# XMC4800-Core.net
KiCad netlist of a schematic drawn in Altium Designer
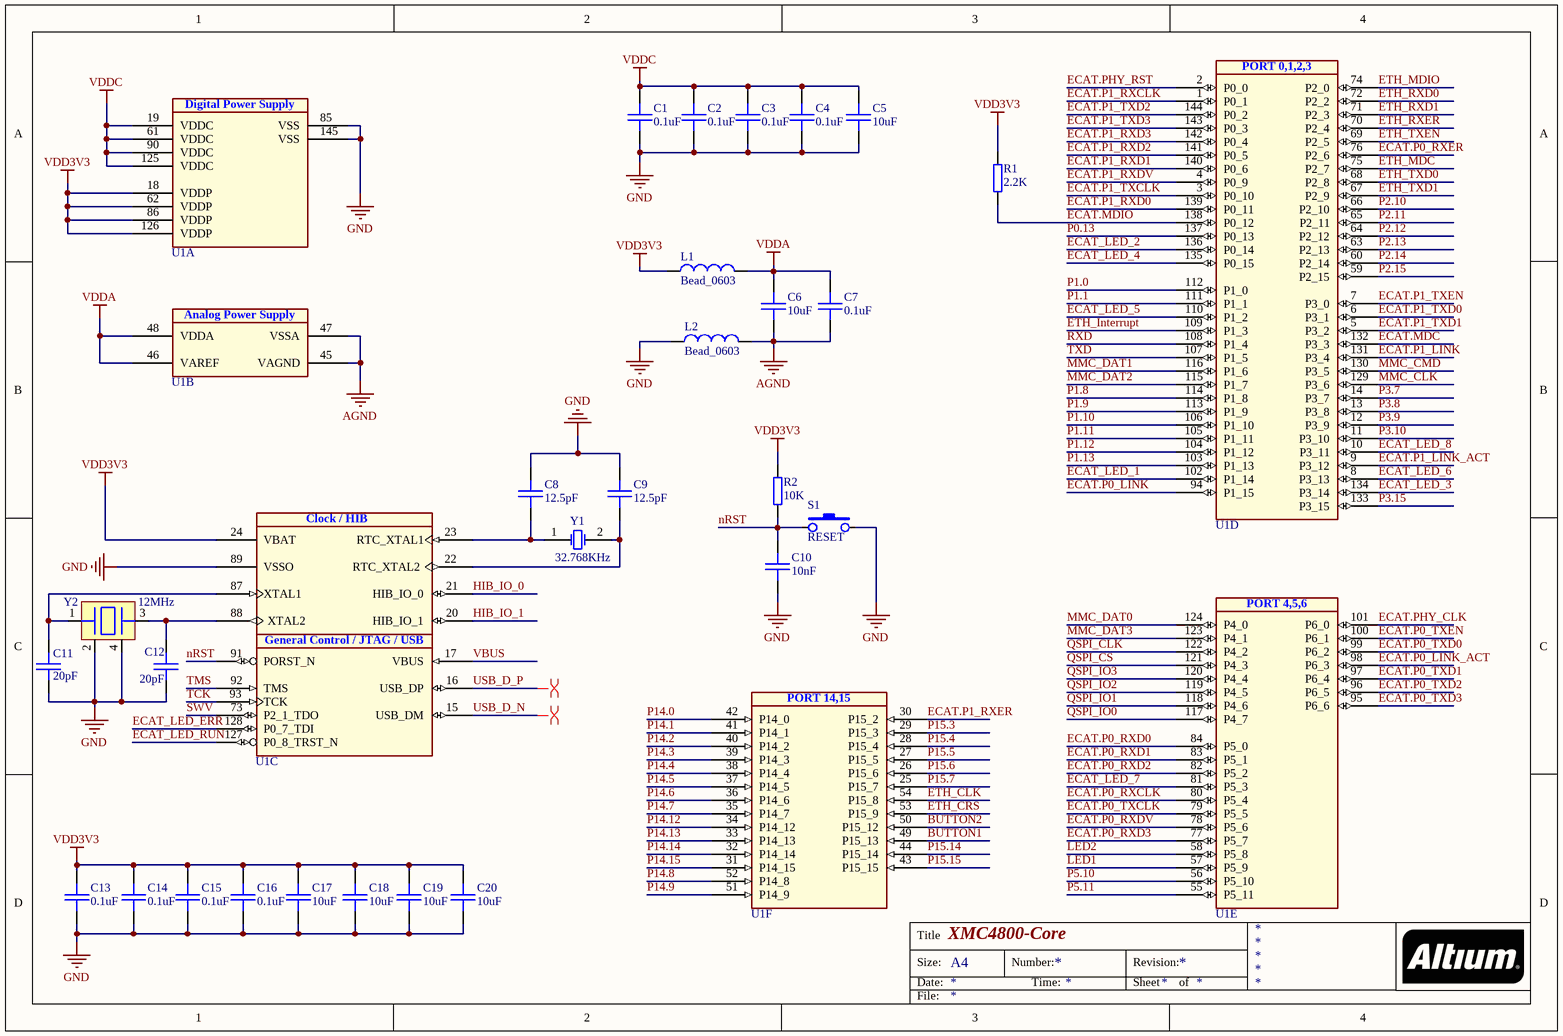
[diagram p0: XMC4800-Core.SchDoc]

(export (version "E")
  (design (tool "Eeschema 10.0.6"))
  (components
    (comp (ref "C1")
      (value "0.1uF")
      (footprint "CAP-0603")
      (description "陶瓷贴片电容0603")
      (fields (field (name "TOLERANCE") "10%") (field (name "VOLTAGE") "50V"))
      (libsource (lib "momo") (part "C_0603"))
    )
    (comp (ref "C2")
      (value "0.1uF")
      (footprint "CAP-0603")
      (description "陶瓷贴片电容0603")
      (fields (field (name "TOLERANCE") "10%") (field (name "VOLTAGE") "50V"))
      (libsource (lib "momo") (part "C_0603"))
    )
    (comp (ref "C3")
      (value "0.1uF")
      (footprint "CAP-0603")
      (description "陶瓷贴片电容0603")
      (fields (field (name "TOLERANCE") "10%") (field (name "VOLTAGE") "50V"))
      (libsource (lib "momo") (part "C_0603"))
    )
    (comp (ref "C4")
      (value "0.1uF")
      (footprint "CAP-0603")
      (description "陶瓷贴片电容0603")
      (fields (field (name "TOLERANCE") "10%") (field (name "VOLTAGE") "50V"))
      (libsource (lib "momo") (part "C_0603"))
    )
    (comp (ref "C5")
      (value "10uF")
      (footprint "CAP-0603")
      (description "陶瓷贴片电容0603")
      (fields (field (name "TOLERANCE") "10%") (field (name "VOLTAGE") "50V"))
      (libsource (lib "momo") (part "C_0603"))
    )
    (comp (ref "C6")
      (value "10uF")
      (footprint "CAP-0603")
      (description "陶瓷贴片电容0603")
      (fields (field (name "TOLERANCE") "10%") (field (name "VOLTAGE") "50V"))
      (libsource (lib "momo") (part "C_0603"))
    )
    (comp (ref "C7")
      (value "0.1uF")
      (footprint "CAP-0603")
      (description "陶瓷贴片电容0603")
      (fields (field (name "TOLERANCE") "10%") (field (name "VOLTAGE") "50V"))
      (libsource (lib "momo") (part "C_0603"))
    )
    (comp (ref "C8")
      (value "12.5pF")
      (footprint "CAP-0603")
      (description "陶瓷贴片电容0603")
      (fields (field (name "TOLERANCE") "10%") (field (name "VOLTAGE") "50V"))
      (libsource (lib "momo") (part "C_0603"))
    )
    (comp (ref "C9")
      (value "12.5pF")
      (footprint "CAP-0603")
      (description "陶瓷贴片电容0603")
      (fields (field (name "TOLERANCE") "10%") (field (name "VOLTAGE") "50V"))
      (libsource (lib "momo") (part "C_0603"))
    )
    (comp (ref "C10")
      (value "10nF")
      (footprint "CAP-0603")
      (description "陶瓷贴片电容0603")
      (fields (field (name "TOLERANCE") "10%") (field (name "VOLTAGE") "50V"))
      (libsource (lib "momo") (part "C_0603"))
    )
    (comp (ref "C11")
      (value "20pF")
      (footprint "CAP-0603")
      (description "陶瓷贴片电容0603")
      (fields (field (name "TOLERANCE") "10%") (field (name "VOLTAGE") "50V"))
      (libsource (lib "momo") (part "C_0603"))
    )
    (comp (ref "C12")
      (value "20pF")
      (footprint "CAP-0603")
      (description "陶瓷贴片电容0603")
      (fields (field (name "TOLERANCE") "10%") (field (name "VOLTAGE") "50V"))
      (libsource (lib "momo") (part "C_0603"))
    )
    (comp (ref "C13")
      (value "0.1uF")
      (footprint "CAP-0603")
      (description "陶瓷贴片电容0603")
      (fields (field (name "TOLERANCE") "10%") (field (name "VOLTAGE") "50V"))
      (libsource (lib "momo") (part "C_0603"))
    )
    (comp (ref "C14")
      (value "0.1uF")
      (footprint "CAP-0603")
      (description "陶瓷贴片电容0603")
      (fields (field (name "TOLERANCE") "10%") (field (name "VOLTAGE") "50V"))
      (libsource (lib "momo") (part "C_0603"))
    )
    (comp (ref "C15")
      (value "0.1uF")
      (footprint "CAP-0603")
      (description "陶瓷贴片电容0603")
      (fields (field (name "TOLERANCE") "10%") (field (name "VOLTAGE") "50V"))
      (libsource (lib "momo") (part "C_0603"))
    )
    (comp (ref "C16")
      (value "0.1uF")
      (footprint "CAP-0603")
      (description "陶瓷贴片电容0603")
      (fields (field (name "TOLERANCE") "10%") (field (name "VOLTAGE") "50V"))
      (libsource (lib "momo") (part "C_0603"))
    )
    (comp (ref "C17")
      (value "10uF")
      (footprint "CAP-0603")
      (description "陶瓷贴片电容0603")
      (fields (field (name "TOLERANCE") "10%") (field (name "VOLTAGE") "50V"))
      (libsource (lib "momo") (part "C_0603"))
    )
    (comp (ref "C18")
      (value "10uF")
      (footprint "CAP-0603")
      (description "陶瓷贴片电容0603")
      (fields (field (name "TOLERANCE") "10%") (field (name "VOLTAGE") "50V"))
      (libsource (lib "momo") (part "C_0603"))
    )
    (comp (ref "C19")
      (value "10uF")
      (footprint "CAP-0603")
      (description "陶瓷贴片电容0603")
      (fields (field (name "TOLERANCE") "10%") (field (name "VOLTAGE") "50V"))
      (libsource (lib "momo") (part "C_0603"))
    )
    (comp (ref "C20")
      (value "10uF")
      (footprint "CAP-0603")
      (description "陶瓷贴片电容0603")
      (fields (field (name "TOLERANCE") "10%") (field (name "VOLTAGE") "50V"))
      (libsource (lib "momo") (part "C_0603"))
    )
    (comp (ref "L1")
      (value "Bead_0603")
      (footprint "L-0603")
      (description "贴片磁珠0603")
      (libsource (lib "momo") (part "Bead_0603"))
    )
    (comp (ref "L2")
      (value "Bead_0603")
      (footprint "L-0603")
      (description "贴片磁珠0603")
      (libsource (lib "momo") (part "Bead_0603"))
    )
    (comp (ref "R1")
      (value "2.2K")
      (footprint "RES-0603")
      (description "贴片电阻0603")
      (fields (field (name "TOLERANCE") "5%") (field (name "VOLTAGE") "50V"))
      (libsource (lib "momo") (part "R_0603"))
    )
    (comp (ref "R2")
      (value "10K")
      (footprint "RES-0603")
      (description "贴片电阻0603")
      (fields (field (name "TOLERANCE") "5%") (field (name "VOLTAGE") "50V"))
      (libsource (lib "momo") (part "R_0603"))
    )
    (comp (ref "S1")
      (value "RESET")
      (footprint "KEY_3X4X2")
      (description "轻触开关3X4X2")
      (libsource (lib "momo") (part "KEY"))
    )
    (comp (ref "U1")
      (value "XMC4800-F144F1024")
      (footprint "QFP50P2200X2200X160-145N-2")
      (fields (field (name "MANUFACTURER") "Infineon Technologies"))
      (libsource (lib "momo") (part "XMC4800-F144F1024"))
    )
    (comp (ref "Y1")
      (value "32.768KHz")
      (footprint "FC-135(3215)")
      (description "32.768KHz时钟晶振")
      (libsource (lib "momo") (part "OSC_32768"))
    )
    (comp (ref "Y2")
      (value "12MHz")
      (footprint "LC-SMD-3225_4P")
      (description "贴片无源晶振(3225)")
      (libsource (lib "momo") (part "XTAL_PASSIVE"))
    )
  )
  (nets
    (net (code "1") (name "/BUTTON1") (class "Default")
      (node (ref "U1") (pin "49") (pinfunction "P15_13_49") (pintype "input"))
    )
    (net (code "2") (name "/BUTTON2") (class "Default")
      (node (ref "U1") (pin "50") (pinfunction "P15_12_50") (pintype "input"))
    )
    (net (code "3") (name "/ECAT.MDC") (class "Default")
      (node (ref "U1") (pin "132") (pinfunction "P3_3_132") (pintype "bidirectional"))
    )
    (net (code "4") (name "/ECAT.MDIO") (class "Default")
      (node (ref "R1") (pin "1") (pinfunction "1_1") (pintype "passive"))
      (node (ref "U1") (pin "138") (pinfunction "P0_12_138") (pintype "bidirectional"))
    )
    (net (code "5") (name "/ECAT.P0_LINK") (class "Default")
      (node (ref "U1") (pin "94") (pinfunction "P1_15_94") (pintype "bidirectional"))
    )
    (net (code "6") (name "/ECAT.P0_LINK_ACT") (class "Default")
      (node (ref "U1") (pin "98") (pinfunction "P6_3_98") (pintype "bidirectional"))
    )
    (net (code "7") (name "/ECAT.P0_RXCLK") (class "Default")
      (node (ref "U1") (pin "80") (pinfunction "P5_4_80") (pintype "bidirectional"))
    )
    (net (code "8") (name "/ECAT.P0_RXD0") (class "Default")
      (node (ref "U1") (pin "84") (pinfunction "P5_0_84") (pintype "bidirectional"))
    )
    (net (code "9") (name "/ECAT.P0_RXD1") (class "Default")
      (node (ref "U1") (pin "83") (pinfunction "P5_1_83") (pintype "bidirectional"))
    )
    (net (code "10") (name "/ECAT.P0_RXD2") (class "Default")
      (node (ref "U1") (pin "82") (pinfunction "P5_2_82") (pintype "bidirectional"))
    )
    (net (code "11") (name "/ECAT.P0_RXD3") (class "Default")
      (node (ref "U1") (pin "77") (pinfunction "P5_7_77") (pintype "bidirectional"))
    )
    (net (code "12") (name "/ECAT.P0_RXDV") (class "Default")
      (node (ref "U1") (pin "78") (pinfunction "P5_6_78") (pintype "bidirectional"))
    )
    (net (code "13") (name "/ECAT.P0_RXER") (class "Default")
      (node (ref "U1") (pin "76") (pinfunction "P2_6_76") (pintype "bidirectional"))
    )
    (net (code "14") (name "/ECAT.P0_TXCLK") (class "Default")
      (node (ref "U1") (pin "79") (pinfunction "P5_5_79") (pintype "bidirectional"))
    )
    (net (code "15") (name "/ECAT.P0_TXD0") (class "Default")
      (node (ref "U1") (pin "99") (pinfunction "P6_2_99") (pintype "bidirectional"))
    )
    (net (code "16") (name "/ECAT.P0_TXD1") (class "Default")
      (node (ref "U1") (pin "97") (pinfunction "P6_4_97") (pintype "bidirectional"))
    )
    (net (code "17") (name "/ECAT.P0_TXD2") (class "Default")
      (node (ref "U1") (pin "96") (pinfunction "P6_5_96") (pintype "bidirectional"))
    )
    (net (code "18") (name "/ECAT.P0_TXD3") (class "Default")
      (node (ref "U1") (pin "95") (pinfunction "P6_6_95") (pintype "bidirectional"))
    )
    (net (code "19") (name "/ECAT.P0_TXEN") (class "Default")
      (node (ref "U1") (pin "100") (pinfunction "P6_1_100") (pintype "bidirectional"))
    )
    (net (code "20") (name "/ECAT.P1_LINK") (class "Default")
      (node (ref "U1") (pin "131") (pinfunction "P3_4_131") (pintype "bidirectional"))
    )
    (net (code "21") (name "/ECAT.P1_LINK_ACT") (class "Default")
      (node (ref "U1") (pin "9") (pinfunction "P3_12_9") (pintype "bidirectional"))
    )
    (net (code "22") (name "/ECAT.P1_RXCLK") (class "Default")
      (node (ref "U1") (pin "1") (pinfunction "P0_1_1") (pintype "bidirectional"))
    )
    (net (code "23") (name "/ECAT.P1_RXD0") (class "Default")
      (node (ref "U1") (pin "139") (pinfunction "P0_11_139") (pintype "bidirectional"))
    )
    (net (code "24") (name "/ECAT.P1_RXD1") (class "Default")
      (node (ref "U1") (pin "140") (pinfunction "P0_6_140") (pintype "bidirectional"))
    )
    (net (code "25") (name "/ECAT.P1_RXD2") (class "Default")
      (node (ref "U1") (pin "141") (pinfunction "P0_5_141") (pintype "bidirectional"))
    )
    (net (code "26") (name "/ECAT.P1_RXD3") (class "Default")
      (node (ref "U1") (pin "142") (pinfunction "P0_4_142") (pintype "bidirectional"))
    )
    (net (code "27") (name "/ECAT.P1_RXDV") (class "Default")
      (node (ref "U1") (pin "4") (pinfunction "P0_9_4") (pintype "bidirectional"))
    )
    (net (code "28") (name "/ECAT.P1_RXER") (class "Default")
      (node (ref "U1") (pin "30") (pinfunction "P15_2_30") (pintype "input"))
    )
    (net (code "29") (name "/ECAT.P1_TXCLK") (class "Default")
      (node (ref "U1") (pin "3") (pinfunction "P0_10_3") (pintype "bidirectional"))
    )
    (net (code "30") (name "/ECAT.P1_TXD0") (class "Default")
      (node (ref "U1") (pin "6") (pinfunction "P3_1_6") (pintype "bidirectional"))
    )
    (net (code "31") (name "/ECAT.P1_TXD1") (class "Default")
      (node (ref "U1") (pin "5") (pinfunction "P3_2_5") (pintype "bidirectional"))
    )
    (net (code "32") (name "/ECAT.P1_TXD2") (class "Default")
      (node (ref "U1") (pin "144") (pinfunction "P0_2_144") (pintype "bidirectional"))
    )
    (net (code "33") (name "/ECAT.P1_TXD3") (class "Default")
      (node (ref "U1") (pin "143") (pinfunction "P0_3_143") (pintype "bidirectional"))
    )
    (net (code "34") (name "/ECAT.P1_TXEN") (class "Default")
      (node (ref "U1") (pin "7") (pinfunction "P3_0_7") (pintype "bidirectional"))
    )
    (net (code "35") (name "/ECAT.PHY_CLK") (class "Default")
      (node (ref "U1") (pin "101") (pinfunction "P6_0_101") (pintype "bidirectional"))
    )
    (net (code "36") (name "/ECAT.PHY_RST") (class "Default")
      (node (ref "U1") (pin "2") (pinfunction "P0_0_2") (pintype "bidirectional"))
    )
    (net (code "37") (name "/ECAT_LED_1") (class "Default")
      (node (ref "U1") (pin "102") (pinfunction "P1_14_102") (pintype "bidirectional"))
    )
    (net (code "38") (name "/ECAT_LED_2") (class "Default")
      (node (ref "U1") (pin "136") (pinfunction "P0_14_136") (pintype "bidirectional"))
    )
    (net (code "39") (name "/ECAT_LED_3") (class "Default")
      (node (ref "U1") (pin "134") (pinfunction "P3_14_134") (pintype "bidirectional"))
    )
    (net (code "40") (name "/ECAT_LED_4") (class "Default")
      (node (ref "U1") (pin "135") (pinfunction "P0_15_135") (pintype "bidirectional"))
    )
    (net (code "41") (name "/ECAT_LED_5") (class "Default")
      (node (ref "U1") (pin "110") (pinfunction "P1_2_110") (pintype "bidirectional"))
    )
    (net (code "42") (name "/ECAT_LED_6") (class "Default")
      (node (ref "U1") (pin "8") (pinfunction "P3_13_8") (pintype "bidirectional"))
    )
    (net (code "43") (name "/ECAT_LED_7") (class "Default")
      (node (ref "U1") (pin "81") (pinfunction "P5_3_81") (pintype "bidirectional"))
    )
    (net (code "44") (name "/ECAT_LED_8") (class "Default")
      (node (ref "U1") (pin "10") (pinfunction "P3_11_10") (pintype "bidirectional"))
    )
    (net (code "45") (name "/ECAT_LED_ERR") (class "Default")
      (node (ref "U1") (pin "128") (pinfunction "P0_7_TDI_128") (pintype "bidirectional"))
    )
    (net (code "46") (name "/ECAT_LED_RUN") (class "Default")
      (node (ref "U1") (pin "127") (pinfunction "P0_8_TRST_N_127") (pintype "bidirectional"))
    )
    (net (code "47") (name "/ETH_CLK") (class "Default")
      (node (ref "U1") (pin "54") (pinfunction "P15_8_54") (pintype "input"))
    )
    (net (code "48") (name "/ETH_CRS") (class "Default")
      (node (ref "U1") (pin "53") (pinfunction "P15_9_53") (pintype "input"))
    )
    (net (code "49") (name "/ETH_Interrupt") (class "Default")
      (node (ref "U1") (pin "109") (pinfunction "P1_3_109") (pintype "bidirectional"))
    )
    (net (code "50") (name "/ETH_MDC") (class "Default")
      (node (ref "U1") (pin "75") (pinfunction "P2_7_75") (pintype "bidirectional"))
    )
    (net (code "51") (name "/ETH_MDIO") (class "Default")
      (node (ref "U1") (pin "74") (pinfunction "P2_0_74") (pintype "bidirectional"))
    )
    (net (code "52") (name "/ETH_RXD0") (class "Default")
      (node (ref "U1") (pin "72") (pinfunction "P2_2_72") (pintype "bidirectional"))
    )
    (net (code "53") (name "/ETH_RXD1") (class "Default")
      (node (ref "U1") (pin "71") (pinfunction "P2_3_71") (pintype "bidirectional"))
    )
    (net (code "54") (name "/ETH_RXER") (class "Default")
      (node (ref "U1") (pin "70") (pinfunction "P2_4_70") (pintype "bidirectional"))
    )
    (net (code "55") (name "/ETH_TXD0") (class "Default")
      (node (ref "U1") (pin "68") (pinfunction "P2_8_68") (pintype "bidirectional"))
    )
    (net (code "56") (name "/ETH_TXD1") (class "Default")
      (node (ref "U1") (pin "67") (pinfunction "P2_9_67") (pintype "bidirectional"))
    )
    (net (code "57") (name "/ETH_TXEN") (class "Default")
      (node (ref "U1") (pin "69") (pinfunction "P2_5_69") (pintype "bidirectional"))
    )
    (net (code "58") (name "/HIB_IO_0") (class "Default")
      (node (ref "U1") (pin "21") (pinfunction "HIB_IO_0_21") (pintype "bidirectional"))
    )
    (net (code "59") (name "/HIB_IO_1") (class "Default")
      (node (ref "U1") (pin "20") (pinfunction "HIB_IO_1_20") (pintype "bidirectional"))
    )
    (net (code "60") (name "/LED1") (class "Default")
      (node (ref "U1") (pin "57") (pinfunction "P5_9_57") (pintype "bidirectional"))
    )
    (net (code "61") (name "/LED2") (class "Default")
      (node (ref "U1") (pin "58") (pinfunction "P5_8_58") (pintype "bidirectional"))
    )
    (net (code "62") (name "/MMC_CLK") (class "Default")
      (node (ref "U1") (pin "129") (pinfunction "P3_6_129") (pintype "bidirectional"))
    )
    (net (code "63") (name "/MMC_CMD") (class "Default")
      (node (ref "U1") (pin "130") (pinfunction "P3_5_130") (pintype "bidirectional"))
    )
    (net (code "64") (name "/MMC_DAT0") (class "Default")
      (node (ref "U1") (pin "124") (pinfunction "P4_0_124") (pintype "bidirectional"))
    )
    (net (code "65") (name "/MMC_DAT1") (class "Default")
      (node (ref "U1") (pin "116") (pinfunction "P1_6_116") (pintype "bidirectional"))
    )
    (net (code "66") (name "/MMC_DAT2") (class "Default")
      (node (ref "U1") (pin "115") (pinfunction "P1_7_115") (pintype "bidirectional"))
    )
    (net (code "67") (name "/MMC_DAT3") (class "Default")
      (node (ref "U1") (pin "123") (pinfunction "P4_1_123") (pintype "bidirectional"))
    )
    (net (code "68") (name "/P0.13") (class "Default")
      (node (ref "U1") (pin "137") (pinfunction "P0_13_137") (pintype "bidirectional"))
    )
    (net (code "69") (name "/P1.0") (class "Default")
      (node (ref "U1") (pin "112") (pinfunction "P1_0_112") (pintype "bidirectional"))
    )
    (net (code "70") (name "/P1.1") (class "Default")
      (node (ref "U1") (pin "111") (pinfunction "P1_1_111") (pintype "bidirectional"))
    )
    (net (code "71") (name "/P1.8") (class "Default")
      (node (ref "U1") (pin "114") (pinfunction "P1_8_114") (pintype "bidirectional"))
    )
    (net (code "72") (name "/P1.9") (class "Default")
      (node (ref "U1") (pin "113") (pinfunction "P1_9_113") (pintype "bidirectional"))
    )
    (net (code "73") (name "/P1.10") (class "Default")
      (node (ref "U1") (pin "106") (pinfunction "P1_10_106") (pintype "bidirectional"))
    )
    (net (code "74") (name "/P1.11") (class "Default")
      (node (ref "U1") (pin "105") (pinfunction "P1_11_105") (pintype "bidirectional"))
    )
    (net (code "75") (name "/P1.12") (class "Default")
      (node (ref "U1") (pin "104") (pinfunction "P1_12_104") (pintype "bidirectional"))
    )
    (net (code "76") (name "/P1.13") (class "Default")
      (node (ref "U1") (pin "103") (pinfunction "P1_13_103") (pintype "bidirectional"))
    )
    (net (code "77") (name "/P2.10") (class "Default")
      (node (ref "U1") (pin "66") (pinfunction "P2_10_66") (pintype "bidirectional"))
    )
    (net (code "78") (name "/P2.11") (class "Default")
      (node (ref "U1") (pin "65") (pinfunction "P2_11_65") (pintype "bidirectional"))
    )
    (net (code "79") (name "/P2.12") (class "Default")
      (node (ref "U1") (pin "64") (pinfunction "P2_12_64") (pintype "bidirectional"))
    )
    (net (code "80") (name "/P2.13") (class "Default")
      (node (ref "U1") (pin "63") (pinfunction "P2_13_63") (pintype "bidirectional"))
    )
    (net (code "81") (name "/P2.14") (class "Default")
      (node (ref "U1") (pin "60") (pinfunction "P2_14_60") (pintype "bidirectional"))
    )
    (net (code "82") (name "/P2.15") (class "Default")
      (node (ref "U1") (pin "59") (pinfunction "P2_15_59") (pintype "bidirectional"))
    )
    (net (code "83") (name "/P3.7") (class "Default")
      (node (ref "U1") (pin "14") (pinfunction "P3_7_14") (pintype "bidirectional"))
    )
    (net (code "84") (name "/P3.8") (class "Default")
      (node (ref "U1") (pin "13") (pinfunction "P3_8_13") (pintype "bidirectional"))
    )
    (net (code "85") (name "/P3.9") (class "Default")
      (node (ref "U1") (pin "12") (pinfunction "P3_9_12") (pintype "bidirectional"))
    )
    (net (code "86") (name "/P3.10") (class "Default")
      (node (ref "U1") (pin "11") (pinfunction "P3_10_11") (pintype "bidirectional"))
    )
    (net (code "87") (name "/P3.15") (class "Default")
      (node (ref "U1") (pin "133") (pinfunction "P3_15_133") (pintype "bidirectional"))
    )
    (net (code "88") (name "/P5.10") (class "Default")
      (node (ref "U1") (pin "56") (pinfunction "P5_10_56") (pintype "bidirectional"))
    )
    (net (code "89") (name "/P5.11") (class "Default")
      (node (ref "U1") (pin "55") (pinfunction "P5_11_55") (pintype "bidirectional"))
    )
    (net (code "90") (name "/P14.0") (class "Default")
      (node (ref "U1") (pin "42") (pinfunction "P14_0_42") (pintype "input"))
    )
    (net (code "91") (name "/P14.1") (class "Default")
      (node (ref "U1") (pin "41") (pinfunction "P14_1_41") (pintype "input"))
    )
    (net (code "92") (name "/P14.2") (class "Default")
      (node (ref "U1") (pin "40") (pinfunction "P14_2_40") (pintype "input"))
    )
    (net (code "93") (name "/P14.3") (class "Default")
      (node (ref "U1") (pin "39") (pinfunction "P14_3_39") (pintype "input"))
    )
    (net (code "94") (name "/P14.4") (class "Default")
      (node (ref "U1") (pin "38") (pinfunction "P14_4_38") (pintype "input"))
    )
    (net (code "95") (name "/P14.5") (class "Default")
      (node (ref "U1") (pin "37") (pinfunction "P14_5_37") (pintype "input"))
    )
    (net (code "96") (name "/P14.6") (class "Default")
      (node (ref "U1") (pin "36") (pinfunction "P14_6_36") (pintype "input"))
    )
    (net (code "97") (name "/P14.7") (class "Default")
      (node (ref "U1") (pin "35") (pinfunction "P14_7_35") (pintype "input"))
    )
    (net (code "98") (name "/P14.8") (class "Default")
      (node (ref "U1") (pin "52") (pinfunction "P14_8_52") (pintype "input"))
    )
    (net (code "99") (name "/P14.9") (class "Default")
      (node (ref "U1") (pin "51") (pinfunction "P14_9_51") (pintype "input"))
    )
    (net (code "100") (name "/P14.12") (class "Default")
      (node (ref "U1") (pin "34") (pinfunction "P14_12_34") (pintype "input"))
    )
    (net (code "101") (name "/P14.13") (class "Default")
      (node (ref "U1") (pin "33") (pinfunction "P14_13_33") (pintype "input"))
    )
    (net (code "102") (name "/P14.14") (class "Default")
      (node (ref "U1") (pin "32") (pinfunction "P14_14_32") (pintype "input"))
    )
    (net (code "103") (name "/P14.15") (class "Default")
      (node (ref "U1") (pin "31") (pinfunction "P14_15_31") (pintype "input"))
    )
    (net (code "104") (name "/P15.3") (class "Default")
      (node (ref "U1") (pin "29") (pinfunction "P15_3_29") (pintype "input"))
    )
    (net (code "105") (name "/P15.4") (class "Default")
      (node (ref "U1") (pin "28") (pinfunction "P15_4_28") (pintype "input"))
    )
    (net (code "106") (name "/P15.5") (class "Default")
      (node (ref "U1") (pin "27") (pinfunction "P15_5_27") (pintype "input"))
    )
    (net (code "107") (name "/P15.6") (class "Default")
      (node (ref "U1") (pin "26") (pinfunction "P15_6_26") (pintype "input"))
    )
    (net (code "108") (name "/P15.7") (class "Default")
      (node (ref "U1") (pin "25") (pinfunction "P15_7_25") (pintype "input"))
    )
    (net (code "109") (name "/P15.14") (class "Default")
      (node (ref "U1") (pin "44") (pinfunction "P15_14_44") (pintype "input"))
    )
    (net (code "110") (name "/P15.15") (class "Default")
      (node (ref "U1") (pin "43") (pinfunction "P15_15_43") (pintype "input"))
    )
    (net (code "111") (name "/QSPI_CLK") (class "Default")
      (node (ref "U1") (pin "122") (pinfunction "P4_2_122") (pintype "bidirectional"))
    )
    (net (code "112") (name "/QSPI_CS") (class "Default")
      (node (ref "U1") (pin "121") (pinfunction "P4_3_121") (pintype "bidirectional"))
    )
    (net (code "113") (name "/QSPI_IO0") (class "Default")
      (node (ref "U1") (pin "117") (pinfunction "P4_7_117") (pintype "bidirectional"))
    )
    (net (code "114") (name "/QSPI_IO1") (class "Default")
      (node (ref "U1") (pin "118") (pinfunction "P4_6_118") (pintype "bidirectional"))
    )
    (net (code "115") (name "/QSPI_IO2") (class "Default")
      (node (ref "U1") (pin "119") (pinfunction "P4_5_119") (pintype "bidirectional"))
    )
    (net (code "116") (name "/QSPI_IO3") (class "Default")
      (node (ref "U1") (pin "120") (pinfunction "P4_4_120") (pintype "bidirectional"))
    )
    (net (code "117") (name "/RXD") (class "Default")
      (node (ref "U1") (pin "108") (pinfunction "P1_4_108") (pintype "bidirectional"))
    )
    (net (code "118") (name "/SWV") (class "Default")
      (node (ref "U1") (pin "73") (pinfunction "P2_1_TDO_73") (pintype "bidirectional"))
    )
    (net (code "119") (name "/TCK") (class "Default")
      (node (ref "U1") (pin "93") (pinfunction "TCK_93") (pintype "input"))
    )
    (net (code "120") (name "/TMS") (class "Default")
      (node (ref "U1") (pin "92") (pinfunction "TMS_92") (pintype "input"))
    )
    (net (code "121") (name "/TXD") (class "Default")
      (node (ref "U1") (pin "107") (pinfunction "P1_5_107") (pintype "bidirectional"))
    )
    (net (code "122") (name "/USB_D_N") (class "Default")
      (node (ref "U1") (pin "15") (pinfunction "USB_DM_15") (pintype "bidirectional"))
    )
    (net (code "123") (name "/USB_D_P") (class "Default")
      (node (ref "U1") (pin "16") (pinfunction "USB_DP_16") (pintype "bidirectional"))
    )
    (net (code "124") (name "/VBUS") (class "Default")
      (node (ref "U1") (pin "17") (pinfunction "VBUS_17") (pintype "input"))
    )
    (net (code "125") (name "/nRST") (class "Default")
      (node (ref "C10") (pin "1") (pinfunction "1_1") (pintype "passive"))
      (node (ref "R2") (pin "1") (pinfunction "1_1") (pintype "passive"))
      (node (ref "S1") (pin "1") (pinfunction "1_1") (pintype "passive"))
      (node (ref "U1") (pin "91") (pinfunction "PORST_N_91") (pintype "bidirectional"))
    )
    (net (code "126") (name "AGND") (class "Default")
      (node (ref "C6") (pin "2") (pinfunction "2_2") (pintype "passive"))
      (node (ref "C7") (pin "2") (pinfunction "2_2") (pintype "passive"))
      (node (ref "L2") (pin "2") (pinfunction "2_2") (pintype "passive"))
      (node (ref "U1") (pin "45") (pinfunction "VAGND_45") (pintype "power_in"))
      (node (ref "U1") (pin "47") (pinfunction "VSSA_47") (pintype "power_in"))
    )
    (net (code "127") (name "GND") (class "Default")
      (node (ref "C1") (pin "2") (pinfunction "2_2") (pintype "passive"))
      (node (ref "C10") (pin "2") (pinfunction "2_2") (pintype "passive"))
      (node (ref "C11") (pin "2") (pinfunction "2_2") (pintype "passive"))
      (node (ref "C12") (pin "2") (pinfunction "2_2") (pintype "passive"))
      (node (ref "C13") (pin "2") (pinfunction "2_2") (pintype "passive"))
      (node (ref "C14") (pin "2") (pinfunction "2_2") (pintype "passive"))
      (node (ref "C15") (pin "2") (pinfunction "2_2") (pintype "passive"))
      (node (ref "C16") (pin "2") (pinfunction "2_2") (pintype "passive"))
      (node (ref "C17") (pin "2") (pinfunction "2_2") (pintype "passive"))
      (node (ref "C18") (pin "2") (pinfunction "2_2") (pintype "passive"))
      (node (ref "C19") (pin "2") (pinfunction "2_2") (pintype "passive"))
      (node (ref "C2") (pin "2") (pinfunction "2_2") (pintype "passive"))
      (node (ref "C20") (pin "2") (pinfunction "2_2") (pintype "passive"))
      (node (ref "C3") (pin "2") (pinfunction "2_2") (pintype "passive"))
      (node (ref "C4") (pin "2") (pinfunction "2_2") (pintype "passive"))
      (node (ref "C5") (pin "2") (pinfunction "2_2") (pintype "passive"))
      (node (ref "C8") (pin "1") (pinfunction "1_1") (pintype "passive"))
      (node (ref "C9") (pin "1") (pinfunction "1_1") (pintype "passive"))
      (node (ref "L2") (pin "1") (pinfunction "1_1") (pintype "passive"))
      (node (ref "S1") (pin "2") (pinfunction "2_2") (pintype "passive"))
      (node (ref "U1") (pin "145") (pinfunction "VSS_145") (pintype "power_in"))
      (node (ref "U1") (pin "85") (pinfunction "VSS_85") (pintype "power_in"))
      (node (ref "U1") (pin "89") (pinfunction "VSSO_89") (pintype "power_in"))
      (node (ref "Y2") (pin "2") (pinfunction "2_2") (pintype "passive"))
      (node (ref "Y2") (pin "4") (pinfunction "4_4") (pintype "passive"))
    )
    (net (code "128") (name "Net-(U1C-RTC_XTAL1)") (class "Default")
      (node (ref "C8") (pin "2") (pinfunction "2_2") (pintype "passive"))
      (node (ref "U1") (pin "23") (pinfunction "RTC_XTAL1_23") (pintype "input"))
      (node (ref "Y1") (pin "1") (pinfunction "OSC1_1") (pintype "passive"))
    )
    (net (code "129") (name "Net-(U1C-RTC_XTAL2)") (class "Default")
      (node (ref "C9") (pin "2") (pinfunction "2_2") (pintype "passive"))
      (node (ref "U1") (pin "22") (pinfunction "RTC_XTAL2_22") (pintype "output"))
      (node (ref "Y1") (pin "2") (pinfunction "OSC2_2") (pintype "passive"))
    )
    (net (code "130") (name "Net-(U1C-XTAL1)") (class "Default")
      (node (ref "C11") (pin "1") (pinfunction "1_1") (pintype "passive"))
      (node (ref "U1") (pin "87") (pinfunction "XTAL1_87") (pintype "input"))
      (node (ref "Y2") (pin "1") (pinfunction "1_1") (pintype "passive"))
    )
    (net (code "131") (name "Net-(U1C-XTAL2)") (class "Default")
      (node (ref "C12") (pin "1") (pinfunction "1_1") (pintype "passive"))
      (node (ref "U1") (pin "88") (pinfunction "XTAL2_88") (pintype "output"))
      (node (ref "Y2") (pin "3") (pinfunction "3_3") (pintype "passive"))
    )
    (net (code "132") (name "VDD3V3") (class "Default")
      (node (ref "C13") (pin "1") (pinfunction "1_1") (pintype "passive"))
      (node (ref "C14") (pin "1") (pinfunction "1_1") (pintype "passive"))
      (node (ref "C15") (pin "1") (pinfunction "1_1") (pintype "passive"))
      (node (ref "C16") (pin "1") (pinfunction "1_1") (pintype "passive"))
      (node (ref "C17") (pin "1") (pinfunction "1_1") (pintype "passive"))
      (node (ref "C18") (pin "1") (pinfunction "1_1") (pintype "passive"))
      (node (ref "C19") (pin "1") (pinfunction "1_1") (pintype "passive"))
      (node (ref "C20") (pin "1") (pinfunction "1_1") (pintype "passive"))
      (node (ref "L1") (pin "1") (pinfunction "1_1") (pintype "passive"))
      (node (ref "R1") (pin "2") (pinfunction "2_2") (pintype "passive"))
      (node (ref "R2") (pin "2") (pinfunction "2_2") (pintype "passive"))
      (node (ref "U1") (pin "126") (pinfunction "VDDP_126") (pintype "power_in"))
      (node (ref "U1") (pin "18") (pinfunction "VDDP_18") (pintype "power_in"))
      (node (ref "U1") (pin "24") (pinfunction "VBAT_24") (pintype "power_in"))
      (node (ref "U1") (pin "62") (pinfunction "VDDP_62") (pintype "power_in"))
      (node (ref "U1") (pin "86") (pinfunction "VDDP_86") (pintype "power_in"))
    )
    (net (code "133") (name "VDDA") (class "Default")
      (node (ref "C6") (pin "1") (pinfunction "1_1") (pintype "passive"))
      (node (ref "C7") (pin "1") (pinfunction "1_1") (pintype "passive"))
      (node (ref "L1") (pin "2") (pinfunction "2_2") (pintype "passive"))
      (node (ref "U1") (pin "46") (pinfunction "VAREF_46") (pintype "power_in"))
      (node (ref "U1") (pin "48") (pinfunction "VDDA_48") (pintype "power_in"))
    )
    (net (code "134") (name "VDDC") (class "Default")
      (node (ref "C1") (pin "1") (pinfunction "1_1") (pintype "passive"))
      (node (ref "C2") (pin "1") (pinfunction "1_1") (pintype "passive"))
      (node (ref "C3") (pin "1") (pinfunction "1_1") (pintype "passive"))
      (node (ref "C4") (pin "1") (pinfunction "1_1") (pintype "passive"))
      (node (ref "C5") (pin "1") (pinfunction "1_1") (pintype "passive"))
      (node (ref "U1") (pin "125") (pinfunction "VDDC_125") (pintype "power_in"))
      (node (ref "U1") (pin "19") (pinfunction "VDDC_19") (pintype "power_in"))
      (node (ref "U1") (pin "61") (pinfunction "VDDC_61") (pintype "power_in"))
      (node (ref "U1") (pin "90") (pinfunction "VDDC_90") (pintype "power_in"))
    )
  )
)
